# led_analog_watch_mvmt_v1_2.net
KiCad netlist of a schematic drawn in EAGLE
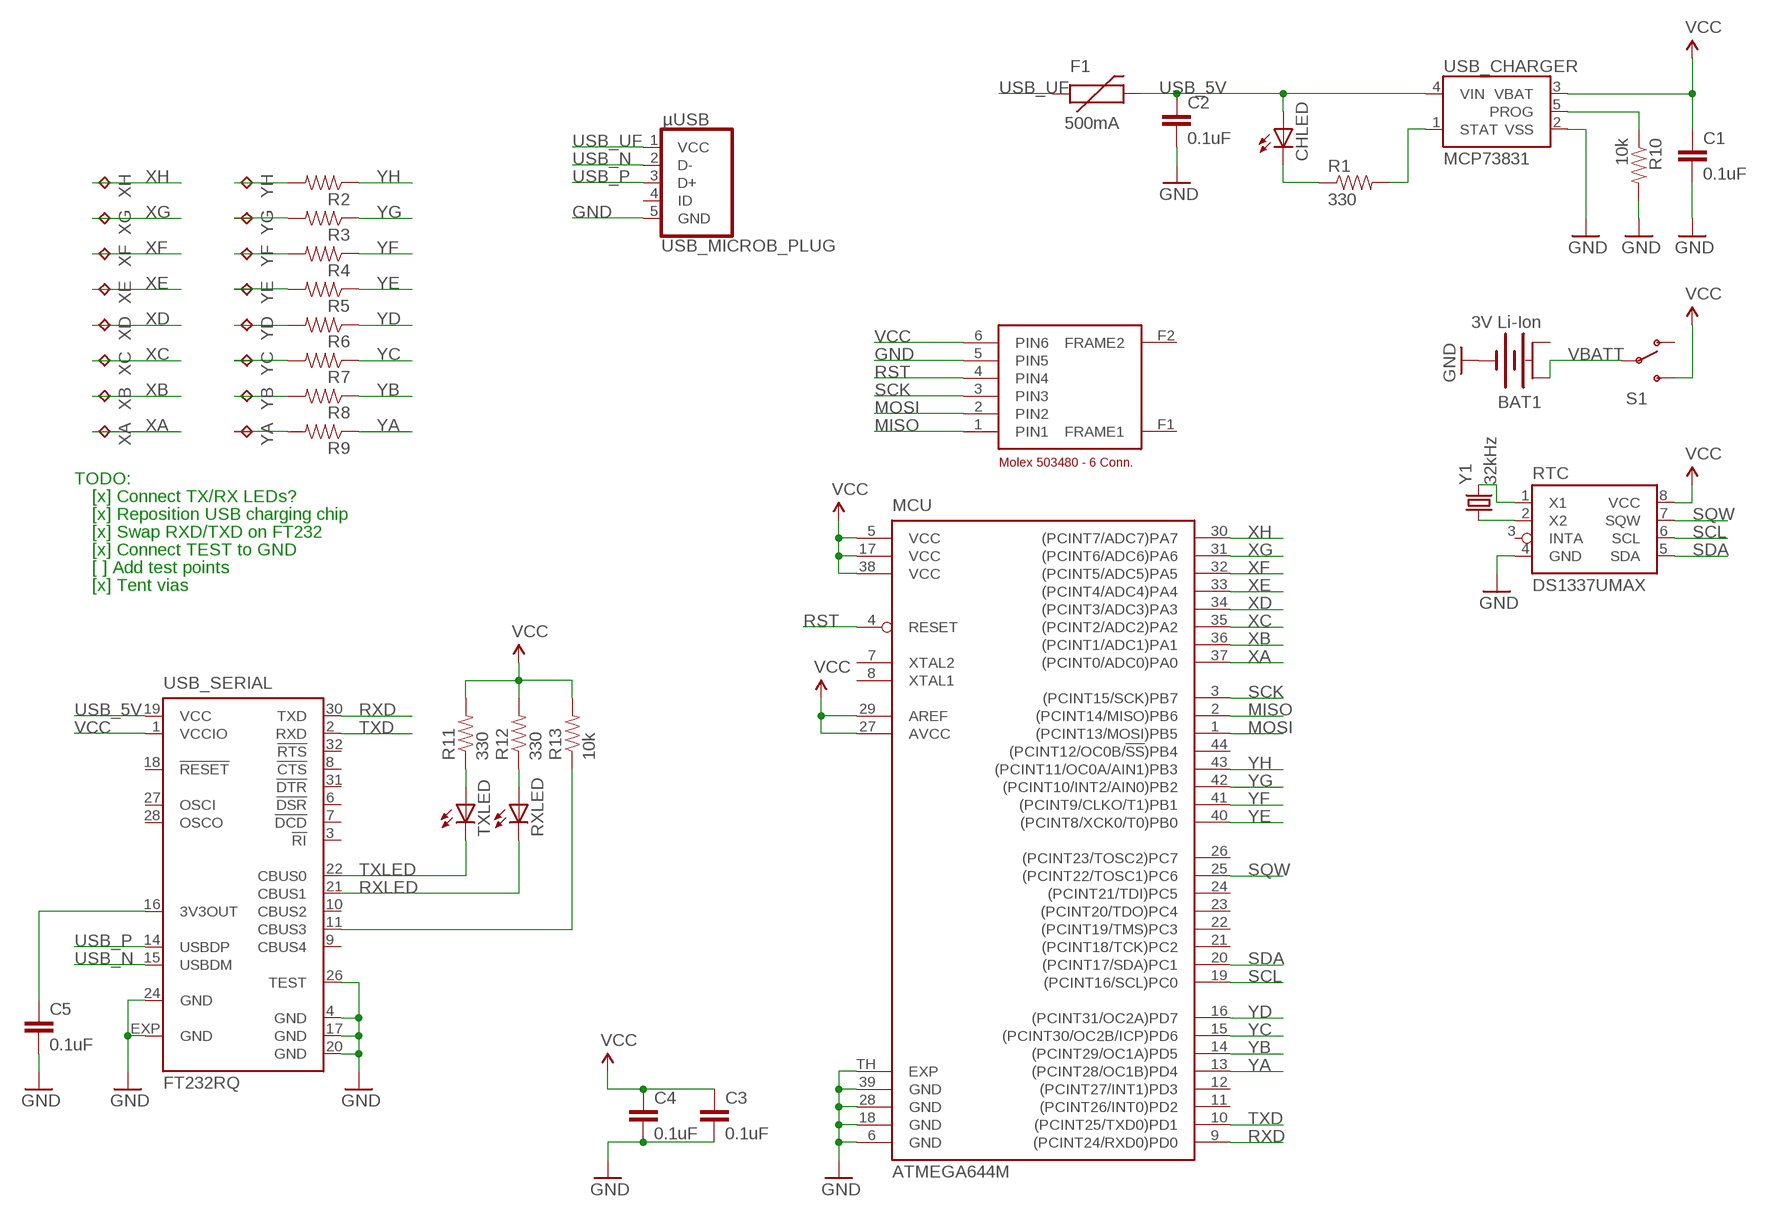
[diagram p0: schematic, sheet 1]

(export (version "E")
  (design (tool "Eeschema 10.0.6"))
  (components
    (comp (ref "BAT1")
      (value "3V Li-Ion")
      (footprint "eagle-import:BATTCON_245MM_PTH")
      (libsource (lib "eagle-import") (part "BATTERY245PTH"))
    )
    (comp (ref "C1")
      (value "0.1uF")
      (footprint "eagle-import:0603-CAP")
      (libsource (lib "eagle-import") (part "CAP-0603"))
    )
    (comp (ref "C2")
      (value "0.1uF")
      (footprint "eagle-import:0603-CAP")
      (libsource (lib "eagle-import") (part "CAP-0603"))
    )
    (comp (ref "C3")
      (value "0.1uF")
      (footprint "eagle-import:0603-CAP")
      (libsource (lib "eagle-import") (part "CAP-0603"))
    )
    (comp (ref "C4")
      (value "0.1uF")
      (footprint "eagle-import:0603-CAP")
      (libsource (lib "eagle-import") (part "CAP-0603"))
    )
    (comp (ref "C5")
      (value "0.1uF")
      (footprint "eagle-import:0603-CAP")
      (libsource (lib "eagle-import") (part "CAP-0603"))
    )
    (comp (ref "CHLED")
      (value "LED-0402")
      (footprint "eagle-import:0402")
      (libsource (lib "eagle-import") (part "LED-0402"))
    )
    (comp (ref "F1")
      (value "500mA")
      (footprint "eagle-import:0603")
      (libsource (lib "eagle-import") (part "PTC0603"))
    )
    (comp (ref "MCU")
      (value "ATMEGA644M")
      (footprint "eagle-import:MLF44-TH")
      (fields (field (name "MPN") "ATMEGA644P-20MU"))
      (libsource (lib "eagle-import") (part "ATMEGA644M"))
    )
    (comp (ref "R1")
      (value "330")
      (footprint "eagle-import:0603")
      (libsource (lib "eagle-import") (part "RESISTOR-0603"))
    )
    (comp (ref "R2")
      (value "RESISTOR-0603")
      (footprint "eagle-import:0603")
      (libsource (lib "eagle-import") (part "RESISTOR-0603"))
    )
    (comp (ref "R3")
      (value "RESISTOR-0603")
      (footprint "eagle-import:0603")
      (libsource (lib "eagle-import") (part "RESISTOR-0603"))
    )
    (comp (ref "R4")
      (value "RESISTOR-0603")
      (footprint "eagle-import:0603")
      (libsource (lib "eagle-import") (part "RESISTOR-0603"))
    )
    (comp (ref "R5")
      (value "RESISTOR-0603")
      (footprint "eagle-import:0603")
      (libsource (lib "eagle-import") (part "RESISTOR-0603"))
    )
    (comp (ref "R6")
      (value "RESISTOR-0603")
      (footprint "eagle-import:0603")
      (libsource (lib "eagle-import") (part "RESISTOR-0603"))
    )
    (comp (ref "R7")
      (value "RESISTOR-0603")
      (footprint "eagle-import:0603")
      (libsource (lib "eagle-import") (part "RESISTOR-0603"))
    )
    (comp (ref "R8")
      (value "RESISTOR-0603")
      (footprint "eagle-import:0603")
      (libsource (lib "eagle-import") (part "RESISTOR-0603"))
    )
    (comp (ref "R9")
      (value "RESISTOR-0603")
      (footprint "eagle-import:0603")
      (libsource (lib "eagle-import") (part "RESISTOR-0603"))
    )
    (comp (ref "R10")
      (value "10k")
      (footprint "eagle-import:0603")
      (libsource (lib "eagle-import") (part "RESISTOR-0603"))
    )
    (comp (ref "R11")
      (value "330")
      (footprint "eagle-import:0603")
      (libsource (lib "eagle-import") (part "RESISTOR-0603"))
    )
    (comp (ref "R12")
      (value "330")
      (footprint "eagle-import:0603")
      (libsource (lib "eagle-import") (part "RESISTOR-0603"))
    )
    (comp (ref "R13")
      (value "10k")
      (footprint "eagle-import:0603")
      (libsource (lib "eagle-import") (part "RESISTOR-0603"))
    )
    (comp (ref "RTC")
      (value "DS1337UMAX")
      (footprint "eagle-import:UMAX8")
      (libsource (lib "eagle-import") (part "DS1337UMAX"))
    )
    (comp (ref "RXLED")
      (value "LED-0402")
      (footprint "eagle-import:0402")
      (libsource (lib "eagle-import") (part "LED-0402"))
    )
    (comp (ref "S1")
      (value "SWITCH-SPSTMA12R")
      (footprint "eagle-import:SWITCH-MA12R")
      (libsource (lib "eagle-import") (part "SWITCH-SPSTMA12R"))
    )
    (comp (ref "TXLED")
      (value "LED-0402")
      (footprint "eagle-import:0402")
      (libsource (lib "eagle-import") (part "LED-0402"))
    )
    (comp (ref "U$2")
      (value "MOLEX_503480")
      (footprint "eagle-import:MOLEX_503480")
      (libsource (lib "eagle-import") (part "MOLEX_503480"))
    )
    (comp (ref "USB_CHARGER")
      (value "MCP73831")
      (footprint "eagle-import:SOT23-5")
      (libsource (lib "eagle-import") (part "MCP73831"))
    )
    (comp (ref "USB_SERIAL")
      (value "FT232RQ")
      (footprint "eagle-import:QFN32")
      (libsource (lib "eagle-import") (part "FT232RQ"))
    )
    (comp (ref "XA")
      (value "TPTP20R")
      (footprint "eagle-import:TP20R")
      (libsource (lib "eagle-import") (part "TPTP20R"))
    )
    (comp (ref "XB")
      (value "TPTP20R")
      (footprint "eagle-import:TP20R")
      (libsource (lib "eagle-import") (part "TPTP20R"))
    )
    (comp (ref "XC")
      (value "TPTP20R")
      (footprint "eagle-import:TP20R")
      (libsource (lib "eagle-import") (part "TPTP20R"))
    )
    (comp (ref "XD")
      (value "TPTP20R")
      (footprint "eagle-import:TP20R")
      (libsource (lib "eagle-import") (part "TPTP20R"))
    )
    (comp (ref "XE")
      (value "TPTP20R")
      (footprint "eagle-import:TP20R")
      (libsource (lib "eagle-import") (part "TPTP20R"))
    )
    (comp (ref "XF")
      (value "TPTP20R")
      (footprint "eagle-import:TP20R")
      (libsource (lib "eagle-import") (part "TPTP20R"))
    )
    (comp (ref "XG")
      (value "TPTP20R")
      (footprint "eagle-import:TP20R")
      (libsource (lib "eagle-import") (part "TPTP20R"))
    )
    (comp (ref "XH")
      (value "TPTP20R")
      (footprint "eagle-import:TP20R")
      (libsource (lib "eagle-import") (part "TPTP20R"))
    )
    (comp (ref "Y1")
      (value "32kHz")
      (footprint "eagle-import:CRYSTAL-ABS10-SMD")
      (libsource (lib "eagle-import") (part "CRYSTALABS10"))
    )
    (comp (ref "YA")
      (value "TPTP20R")
      (footprint "eagle-import:TP20R")
      (libsource (lib "eagle-import") (part "TPTP20R"))
    )
    (comp (ref "YB")
      (value "TPTP20R")
      (footprint "eagle-import:TP20R")
      (libsource (lib "eagle-import") (part "TPTP20R"))
    )
    (comp (ref "YC")
      (value "TPTP20R")
      (footprint "eagle-import:TP20R")
      (libsource (lib "eagle-import") (part "TPTP20R"))
    )
    (comp (ref "YD")
      (value "TPTP20R")
      (footprint "eagle-import:TP20R")
      (libsource (lib "eagle-import") (part "TPTP20R"))
    )
    (comp (ref "YE")
      (value "TPTP20R")
      (footprint "eagle-import:TP20R")
      (libsource (lib "eagle-import") (part "TPTP20R"))
    )
    (comp (ref "YF")
      (value "TPTP20R")
      (footprint "eagle-import:TP20R")
      (libsource (lib "eagle-import") (part "TPTP20R"))
    )
    (comp (ref "YG")
      (value "TPTP20R")
      (footprint "eagle-import:TP20R")
      (libsource (lib "eagle-import") (part "TPTP20R"))
    )
    (comp (ref "YH")
      (value "TPTP20R")
      (footprint "eagle-import:TP20R")
      (libsource (lib "eagle-import") (part "TPTP20R"))
    )
    (comp (ref "µUSB")
      (value "USB_MICROB_PLUG")
      (footprint "eagle-import:USB_MICRO_B_TYCO")
      (libsource (lib "eagle-import") (part "USB_MICROB_PLUG"))
    )
  )
  (nets
    (net (code "1") (name "/+B") (class "Default")
      (node (ref "BAT1") (pin "1") (pinfunction "+B_1") (pintype "power_in"))
    )
    (net (code "2") (name "/MISO") (class "Default")
      (node (ref "MCU") (pin "2") (pinfunction "(PCINT14/MISO)PB6_2") (pintype "bidirectional"))
      (node (ref "U$2") (pin "1") (pinfunction "PIN1_1") (pintype "bidirectional"))
    )
    (net (code "3") (name "/MOSI") (class "Default")
      (node (ref "MCU") (pin "1") (pinfunction "(PCINT13/MOSI)PB5_1") (pintype "bidirectional"))
      (node (ref "U$2") (pin "2") (pinfunction "PIN2_2") (pintype "bidirectional"))
    )
    (net (code "4") (name "/RST") (class "Default")
      (node (ref "MCU") (pin "4") (pinfunction "RESET_4") (pintype "input"))
      (node (ref "U$2") (pin "4") (pinfunction "PIN4_4") (pintype "bidirectional"))
    )
    (net (code "5") (name "/RXD") (class "Default")
      (node (ref "MCU") (pin "9") (pinfunction "(PCINT24/RXD0)PD0_9") (pintype "bidirectional"))
      (node (ref "USB_SERIAL") (pin "30") (pinfunction "TXD_30") (pintype "output"))
    )
    (net (code "6") (name "/RXLED") (class "Default")
      (node (ref "RXLED") (pin "2") (pinfunction "C_2") (pintype "passive"))
      (node (ref "USB_SERIAL") (pin "21") (pinfunction "CBUS1_21") (pintype "bidirectional"))
    )
    (net (code "7") (name "/SCK") (class "Default")
      (node (ref "MCU") (pin "3") (pinfunction "(PCINT15/SCK)PB7_3") (pintype "bidirectional"))
      (node (ref "U$2") (pin "3") (pinfunction "PIN3_3") (pintype "bidirectional"))
    )
    (net (code "8") (name "/SCL") (class "Default")
      (node (ref "MCU") (pin "19") (pinfunction "(PCINT16/SCL)PC0_19") (pintype "output"))
      (node (ref "RTC") (pin "6") (pinfunction "SCL_6") (pintype "bidirectional"))
    )
    (net (code "9") (name "/SDA") (class "Default")
      (node (ref "MCU") (pin "20") (pinfunction "(PCINT17/SDA)PC1_20") (pintype "output"))
      (node (ref "RTC") (pin "5") (pinfunction "SDA_5") (pintype "bidirectional"))
    )
    (net (code "10") (name "/SQW") (class "Default")
      (node (ref "MCU") (pin "25") (pinfunction "(PCINT22/TOSC1)PC6_25") (pintype "output"))
      (node (ref "RTC") (pin "7") (pinfunction "SQW_7") (pintype "bidirectional"))
    )
    (net (code "11") (name "/TXD") (class "Default")
      (node (ref "MCU") (pin "10") (pinfunction "(PCINT25/TXD0)PD1_10") (pintype "bidirectional"))
      (node (ref "USB_SERIAL") (pin "2") (pinfunction "RXD_2") (pintype "input"))
    )
    (net (code "12") (name "/TXLED") (class "Default")
      (node (ref "TXLED") (pin "2") (pinfunction "C_2") (pintype "passive"))
      (node (ref "USB_SERIAL") (pin "22") (pinfunction "CBUS0_22") (pintype "bidirectional"))
    )
    (net (code "13") (name "/USB_5V") (class "Default")
      (node (ref "C2") (pin "1") (pinfunction "1_1") (pintype "passive"))
      (node (ref "CHLED") (pin "1") (pinfunction "A_1") (pintype "passive"))
      (node (ref "F1") (pin "2") (pinfunction "2_2") (pintype "bidirectional"))
      (node (ref "USB_CHARGER") (pin "4") (pinfunction "VIN_4") (pintype "power_in"))
      (node (ref "USB_SERIAL") (pin "19") (pinfunction "VCC_19") (pintype "power_in"))
    )
    (net (code "14") (name "/USB_N") (class "Default")
      (node (ref "USB_SERIAL") (pin "15") (pinfunction "USBDM_15") (pintype "bidirectional"))
      (node (ref "µUSB") (pin "2") (pinfunction "D-_2") (pintype "bidirectional"))
    )
    (net (code "15") (name "/USB_P") (class "Default")
      (node (ref "USB_SERIAL") (pin "14") (pinfunction "USBDP_14") (pintype "bidirectional"))
      (node (ref "µUSB") (pin "3") (pinfunction "D+_3") (pintype "bidirectional"))
    )
    (net (code "16") (name "/USB_UF") (class "Default")
      (node (ref "F1") (pin "1") (pinfunction "1_1") (pintype "bidirectional"))
      (node (ref "µUSB") (pin "1") (pinfunction "VCC_1") (pintype "bidirectional"))
    )
    (net (code "17") (name "/VBATT") (class "Default")
      (node (ref "BAT1") (pin "3") (pinfunction "+A_3") (pintype "power_in"))
      (node (ref "S1") (pin "2") (pinfunction "P_2") (pintype "passive"))
    )
    (net (code "18") (name "/XA") (class "Default")
      (node (ref "MCU") (pin "37") (pinfunction "(PCINT0/ADC0)PA0_37") (pintype "bidirectional"))
      (node (ref "XA") (pin "TP") (pinfunction "TP_TP") (pintype "input"))
    )
    (net (code "19") (name "/XB") (class "Default")
      (node (ref "MCU") (pin "36") (pinfunction "(PCINT1/ADC1)PA1_36") (pintype "bidirectional"))
      (node (ref "XB") (pin "TP") (pinfunction "TP_TP") (pintype "input"))
    )
    (net (code "20") (name "/XC") (class "Default")
      (node (ref "MCU") (pin "35") (pinfunction "(PCINT2/ADC2)PA2_35") (pintype "bidirectional"))
      (node (ref "XC") (pin "TP") (pinfunction "TP_TP") (pintype "input"))
    )
    (net (code "21") (name "/XD") (class "Default")
      (node (ref "MCU") (pin "34") (pinfunction "(PCINT3/ADC3)PA3_34") (pintype "bidirectional"))
      (node (ref "XD") (pin "TP") (pinfunction "TP_TP") (pintype "input"))
    )
    (net (code "22") (name "/XE") (class "Default")
      (node (ref "MCU") (pin "33") (pinfunction "(PCINT4/ADC4)PA4_33") (pintype "bidirectional"))
      (node (ref "XE") (pin "TP") (pinfunction "TP_TP") (pintype "input"))
    )
    (net (code "23") (name "/XF") (class "Default")
      (node (ref "MCU") (pin "32") (pinfunction "(PCINT5/ADC5)PA5_32") (pintype "bidirectional"))
      (node (ref "XF") (pin "TP") (pinfunction "TP_TP") (pintype "input"))
    )
    (net (code "24") (name "/XG") (class "Default")
      (node (ref "MCU") (pin "31") (pinfunction "(PCINT6/ADC6)PA6_31") (pintype "bidirectional"))
      (node (ref "XG") (pin "TP") (pinfunction "TP_TP") (pintype "input"))
    )
    (net (code "25") (name "/XH") (class "Default")
      (node (ref "MCU") (pin "30") (pinfunction "(PCINT7/ADC7)PA7_30") (pintype "bidirectional"))
      (node (ref "XH") (pin "TP") (pinfunction "TP_TP") (pintype "input"))
    )
    (net (code "26") (name "/YA") (class "Default")
      (node (ref "MCU") (pin "13") (pinfunction "(PCINT28/OC1B)PD4_13") (pintype "bidirectional"))
      (node (ref "R9") (pin "1") (pinfunction "1_1") (pintype "passive"))
    )
    (net (code "27") (name "/YB") (class "Default")
      (node (ref "MCU") (pin "14") (pinfunction "(PCINT29/OC1A)PD5_14") (pintype "bidirectional"))
      (node (ref "R8") (pin "1") (pinfunction "1_1") (pintype "passive"))
    )
    (net (code "28") (name "/YC") (class "Default")
      (node (ref "MCU") (pin "15") (pinfunction "(PCINT30/OC2B/ICP)PD6_15") (pintype "bidirectional"))
      (node (ref "R7") (pin "1") (pinfunction "1_1") (pintype "passive"))
    )
    (net (code "29") (name "/YD") (class "Default")
      (node (ref "MCU") (pin "16") (pinfunction "(PCINT31/OC2A)PD7_16") (pintype "bidirectional"))
      (node (ref "R6") (pin "1") (pinfunction "1_1") (pintype "passive"))
    )
    (net (code "30") (name "/YE") (class "Default")
      (node (ref "MCU") (pin "40") (pinfunction "(PCINT8/XCK0/T0)PB0_40") (pintype "bidirectional"))
      (node (ref "R5") (pin "1") (pinfunction "1_1") (pintype "passive"))
    )
    (net (code "31") (name "/YF") (class "Default")
      (node (ref "MCU") (pin "41") (pinfunction "(PCINT9/CLKO/T1)PB1_41") (pintype "bidirectional"))
      (node (ref "R4") (pin "1") (pinfunction "1_1") (pintype "passive"))
    )
    (net (code "32") (name "/YG") (class "Default")
      (node (ref "MCU") (pin "42") (pinfunction "(PCINT10/INT2/AIN0)PB2_42") (pintype "bidirectional"))
      (node (ref "R3") (pin "1") (pinfunction "1_1") (pintype "passive"))
    )
    (net (code "33") (name "/YH") (class "Default")
      (node (ref "MCU") (pin "43") (pinfunction "(PCINT11/OC0A/AIN1)PB3_43") (pintype "bidirectional"))
      (node (ref "R2") (pin "1") (pinfunction "1_1") (pintype "passive"))
    )
    (net (code "34") (name "GND") (class "Default")
      (node (ref "BAT1") (pin "2") (pinfunction "-_2") (pintype "power_in"))
      (node (ref "C1") (pin "2") (pinfunction "2_2") (pintype "passive"))
      (node (ref "C2") (pin "2") (pinfunction "2_2") (pintype "passive"))
      (node (ref "C3") (pin "2") (pinfunction "2_2") (pintype "passive"))
      (node (ref "C4") (pin "2") (pinfunction "2_2") (pintype "passive"))
      (node (ref "C5") (pin "2") (pinfunction "2_2") (pintype "passive"))
      (node (ref "MCU") (pin "18") (pinfunction "GND_18") (pintype "power_in"))
      (node (ref "MCU") (pin "28") (pinfunction "GND_28") (pintype "power_in"))
      (node (ref "MCU") (pin "39") (pinfunction "GND_39") (pintype "power_in"))
      (node (ref "MCU") (pin "6") (pinfunction "GND_6") (pintype "power_in"))
      (node (ref "MCU") (pin "TH") (pinfunction "EXP_TH") (pintype "power_in"))
      (node (ref "R10") (pin "2") (pinfunction "2_2") (pintype "passive"))
      (node (ref "RTC") (pin "4") (pinfunction "GND_4") (pintype "bidirectional"))
      (node (ref "U$2") (pin "5") (pinfunction "PIN5_5") (pintype "bidirectional"))
      (node (ref "USB_CHARGER") (pin "2") (pinfunction "VSS_2") (pintype "power_in"))
      (node (ref "USB_SERIAL") (pin "17") (pinfunction "GND_17") (pintype "power_in"))
      (node (ref "USB_SERIAL") (pin "20") (pinfunction "GND_20") (pintype "power_in"))
      (node (ref "USB_SERIAL") (pin "24") (pinfunction "GND_24") (pintype "power_in"))
      (node (ref "USB_SERIAL") (pin "26") (pinfunction "TEST_26") (pintype "input"))
      (node (ref "USB_SERIAL") (pin "4") (pinfunction "GND_4") (pintype "power_in"))
      (node (ref "USB_SERIAL") (pin "EXP") (pinfunction "GND_EXP") (pintype "power_in"))
      (node (ref "µUSB") (pin "5") (pinfunction "GND_5") (pintype "bidirectional"))
    )
    (net (code "35") (name "Net-(CHLED-C)") (class "Default")
      (node (ref "CHLED") (pin "2") (pinfunction "C_2") (pintype "passive"))
      (node (ref "R1") (pin "1") (pinfunction "1_1") (pintype "passive"))
    )
    (net (code "36") (name "Net-(R2-Pad2)") (class "Default")
      (node (ref "R2") (pin "2") (pinfunction "2_2") (pintype "passive"))
      (node (ref "YH") (pin "TP") (pinfunction "TP_TP") (pintype "input"))
    )
    (net (code "37") (name "Net-(R3-Pad2)") (class "Default")
      (node (ref "R3") (pin "2") (pinfunction "2_2") (pintype "passive"))
      (node (ref "YG") (pin "TP") (pinfunction "TP_TP") (pintype "input"))
    )
    (net (code "38") (name "Net-(R4-Pad2)") (class "Default")
      (node (ref "R4") (pin "2") (pinfunction "2_2") (pintype "passive"))
      (node (ref "YF") (pin "TP") (pinfunction "TP_TP") (pintype "input"))
    )
    (net (code "39") (name "Net-(R5-Pad2)") (class "Default")
      (node (ref "R5") (pin "2") (pinfunction "2_2") (pintype "passive"))
      (node (ref "YE") (pin "TP") (pinfunction "TP_TP") (pintype "input"))
    )
    (net (code "40") (name "Net-(R6-Pad2)") (class "Default")
      (node (ref "R6") (pin "2") (pinfunction "2_2") (pintype "passive"))
      (node (ref "YD") (pin "TP") (pinfunction "TP_TP") (pintype "input"))
    )
    (net (code "41") (name "Net-(R7-Pad2)") (class "Default")
      (node (ref "R7") (pin "2") (pinfunction "2_2") (pintype "passive"))
      (node (ref "YC") (pin "TP") (pinfunction "TP_TP") (pintype "input"))
    )
    (net (code "42") (name "Net-(R8-Pad2)") (class "Default")
      (node (ref "R8") (pin "2") (pinfunction "2_2") (pintype "passive"))
      (node (ref "YB") (pin "TP") (pinfunction "TP_TP") (pintype "input"))
    )
    (net (code "43") (name "Net-(R9-Pad2)") (class "Default")
      (node (ref "R9") (pin "2") (pinfunction "2_2") (pintype "passive"))
      (node (ref "YA") (pin "TP") (pinfunction "TP_TP") (pintype "input"))
    )
    (net (code "44") (name "Net-(RTC-X1)") (class "Default")
      (node (ref "RTC") (pin "1") (pinfunction "X1_1") (pintype "bidirectional"))
      (node (ref "Y1") (pin "X2") (pinfunction "2_X2") (pintype "passive"))
    )
    (net (code "45") (name "Net-(RTC-X2)") (class "Default")
      (node (ref "RTC") (pin "2") (pinfunction "X2_2") (pintype "bidirectional"))
      (node (ref "Y1") (pin "X1") (pinfunction "1_X1") (pintype "passive"))
    )
    (net (code "46") (name "Net-(RXLED-A)") (class "Default")
      (node (ref "R12") (pin "1") (pinfunction "1_1") (pintype "passive"))
      (node (ref "RXLED") (pin "1") (pinfunction "A_1") (pintype "passive"))
    )
    (net (code "47") (name "Net-(TXLED-A)") (class "Default")
      (node (ref "R11") (pin "1") (pinfunction "1_1") (pintype "passive"))
      (node (ref "TXLED") (pin "1") (pinfunction "A_1") (pintype "passive"))
    )
    (net (code "48") (name "Net-(USB_CHARGER-PROG)") (class "Default")
      (node (ref "R10") (pin "1") (pinfunction "1_1") (pintype "passive"))
      (node (ref "USB_CHARGER") (pin "5") (pinfunction "PROG_5") (pintype "input"))
    )
    (net (code "49") (name "Net-(USB_CHARGER-STAT)") (class "Default")
      (node (ref "R1") (pin "2") (pinfunction "2_2") (pintype "passive"))
      (node (ref "USB_CHARGER") (pin "1") (pinfunction "STAT_1") (pintype "output"))
    )
    (net (code "50") (name "Net-(USB_SERIAL-3V3OUT)") (class "Default")
      (node (ref "C5") (pin "1") (pinfunction "1_1") (pintype "passive"))
      (node (ref "USB_SERIAL") (pin "16") (pinfunction "3V3OUT_16") (pintype "output"))
    )
    (net (code "51") (name "Net-(USB_SERIAL-CBUS3)") (class "Default")
      (node (ref "R13") (pin "1") (pinfunction "1_1") (pintype "passive"))
      (node (ref "USB_SERIAL") (pin "11") (pinfunction "CBUS3_11") (pintype "bidirectional"))
    )
    (net (code "52") (name "VCC") (class "Default")
      (node (ref "C1") (pin "1") (pinfunction "1_1") (pintype "passive"))
      (node (ref "C3") (pin "1") (pinfunction "1_1") (pintype "passive"))
      (node (ref "C4") (pin "1") (pinfunction "1_1") (pintype "passive"))
      (node (ref "MCU") (pin "17") (pinfunction "VCC_17") (pintype "power_in"))
      (node (ref "MCU") (pin "27") (pinfunction "AVCC_27") (pintype "power_in"))
      (node (ref "MCU") (pin "29") (pinfunction "AREF_29") (pintype "passive"))
      (node (ref "MCU") (pin "38") (pinfunction "VCC_38") (pintype "power_in"))
      (node (ref "MCU") (pin "5") (pinfunction "VCC_5") (pintype "power_in"))
      (node (ref "R11") (pin "2") (pinfunction "2_2") (pintype "passive"))
      (node (ref "R12") (pin "2") (pinfunction "2_2") (pintype "passive"))
      (node (ref "R13") (pin "2") (pinfunction "2_2") (pintype "passive"))
      (node (ref "RTC") (pin "8") (pinfunction "VCC_8") (pintype "bidirectional"))
      (node (ref "S1") (pin "3") (pinfunction "S_3") (pintype "passive"))
      (node (ref "U$2") (pin "6") (pinfunction "PIN6_6") (pintype "bidirectional"))
      (node (ref "USB_CHARGER") (pin "3") (pinfunction "VBAT_3") (pintype "power_in"))
      (node (ref "USB_SERIAL") (pin "1") (pinfunction "VCCIO_1") (pintype "power_in"))
    )
    (net (code "53") (name "unconnected-(MCU-(PCINT12{slash}OC0B{slash}~{SS})PB4-Pad44)") (class "Default")
      (node (ref "MCU") (pin "44") (pinfunction "(PCINT12/OC0B/~{SS})PB4_44") (pintype "bidirectional"))
    )
    (net (code "54") (name "unconnected-(MCU-(PCINT18{slash}TCK)PC2-Pad21)") (class "Default")
      (node (ref "MCU") (pin "21") (pinfunction "(PCINT18/TCK)PC2_21") (pintype "output"))
    )
    (net (code "55") (name "unconnected-(MCU-(PCINT19{slash}TMS)PC3-Pad22)") (class "Default")
      (node (ref "MCU") (pin "22") (pinfunction "(PCINT19/TMS)PC3_22") (pintype "output"))
    )
    (net (code "56") (name "unconnected-(MCU-(PCINT20{slash}TDO)PC4-Pad23)") (class "Default")
      (node (ref "MCU") (pin "23") (pinfunction "(PCINT20/TDO)PC4_23") (pintype "output"))
    )
    (net (code "57") (name "unconnected-(MCU-(PCINT21{slash}TDI)PC5-Pad24)") (class "Default")
      (node (ref "MCU") (pin "24") (pinfunction "(PCINT21/TDI)PC5_24") (pintype "output"))
    )
    (net (code "58") (name "unconnected-(MCU-(PCINT23{slash}TOSC2)PC7-Pad26)") (class "Default")
      (node (ref "MCU") (pin "26") (pinfunction "(PCINT23/TOSC2)PC7_26") (pintype "output"))
    )
    (net (code "59") (name "unconnected-(MCU-(PCINT26{slash}INT0)PD2-Pad11)") (class "Default")
      (node (ref "MCU") (pin "11") (pinfunction "(PCINT26/INT0)PD2_11") (pintype "bidirectional"))
    )
    (net (code "60") (name "unconnected-(MCU-(PCINT27{slash}INT1)PD3-Pad12)") (class "Default")
      (node (ref "MCU") (pin "12") (pinfunction "(PCINT27/INT1)PD3_12") (pintype "bidirectional"))
    )
    (net (code "61") (name "unconnected-(MCU-XTAL1-Pad8)") (class "Default")
      (node (ref "MCU") (pin "8") (pinfunction "XTAL1_8") (pintype "bidirectional"))
    )
    (net (code "62") (name "unconnected-(MCU-XTAL2-Pad7)") (class "Default")
      (node (ref "MCU") (pin "7") (pinfunction "XTAL2_7") (pintype "bidirectional"))
    )
    (net (code "63") (name "unconnected-(RTC-INTA-Pad3)") (class "Default")
      (node (ref "RTC") (pin "3") (pinfunction "INTA_3") (pintype "bidirectional"))
    )
    (net (code "64") (name "unconnected-(S1-O-Pad1)") (class "Default")
      (node (ref "S1") (pin "1") (pinfunction "O_1") (pintype "passive"))
    )
    (net (code "65") (name "unconnected-(U$2-FRAME1-PadF1)") (class "Default")
      (node (ref "U$2") (pin "F1") (pinfunction "FRAME1_F1") (pintype "bidirectional"))
    )
    (net (code "66") (name "unconnected-(U$2-FRAME2-PadF2)") (class "Default")
      (node (ref "U$2") (pin "F2") (pinfunction "FRAME2_F2") (pintype "bidirectional"))
    )
    (net (code "67") (name "unconnected-(USB_SERIAL-CBUS2-Pad10)") (class "Default")
      (node (ref "USB_SERIAL") (pin "10") (pinfunction "CBUS2_10") (pintype "bidirectional"))
    )
    (net (code "68") (name "unconnected-(USB_SERIAL-CBUS4-Pad9)") (class "Default")
      (node (ref "USB_SERIAL") (pin "9") (pinfunction "CBUS4_9") (pintype "bidirectional"))
    )
    (net (code "69") (name "unconnected-(USB_SERIAL-OSCI-Pad27)") (class "Default")
      (node (ref "USB_SERIAL") (pin "27") (pinfunction "OSCI_27") (pintype "input"))
    )
    (net (code "70") (name "unconnected-(USB_SERIAL-OSCO-Pad28)") (class "Default")
      (node (ref "USB_SERIAL") (pin "28") (pinfunction "OSCO_28") (pintype "output"))
    )
    (net (code "71") (name "unconnected-(USB_SERIAL-~{CTS}-Pad8)") (class "Default")
      (node (ref "USB_SERIAL") (pin "8") (pinfunction "~{CTS}_8") (pintype "input"))
    )
    (net (code "72") (name "unconnected-(USB_SERIAL-~{DCD}-Pad7)") (class "Default")
      (node (ref "USB_SERIAL") (pin "7") (pinfunction "~{DCD}_7") (pintype "input"))
    )
    (net (code "73") (name "unconnected-(USB_SERIAL-~{DSR}-Pad6)") (class "Default")
      (node (ref "USB_SERIAL") (pin "6") (pinfunction "~{DSR}_6") (pintype "input"))
    )
    (net (code "74") (name "unconnected-(USB_SERIAL-~{DTR}-Pad31)") (class "Default")
      (node (ref "USB_SERIAL") (pin "31") (pinfunction "~{DTR}_31") (pintype "output"))
    )
    (net (code "75") (name "unconnected-(USB_SERIAL-~{RESET}-Pad18)") (class "Default")
      (node (ref "USB_SERIAL") (pin "18") (pinfunction "~{RESET}_18") (pintype "input"))
    )
    (net (code "76") (name "unconnected-(USB_SERIAL-~{RI}-Pad3)") (class "Default")
      (node (ref "USB_SERIAL") (pin "3") (pinfunction "~{RI}_3") (pintype "input"))
    )
    (net (code "77") (name "unconnected-(USB_SERIAL-~{RTS}-Pad32)") (class "Default")
      (node (ref "USB_SERIAL") (pin "32") (pinfunction "~{RTS}_32") (pintype "output"))
    )
    (net (code "78") (name "unconnected-(µUSB-ID-Pad4)") (class "Default")
      (node (ref "µUSB") (pin "4") (pinfunction "ID_4") (pintype "bidirectional"))
    )
  )
)
